# Internal_Breakout.net
KiCad netlist of a schematic drawn in EAGLE
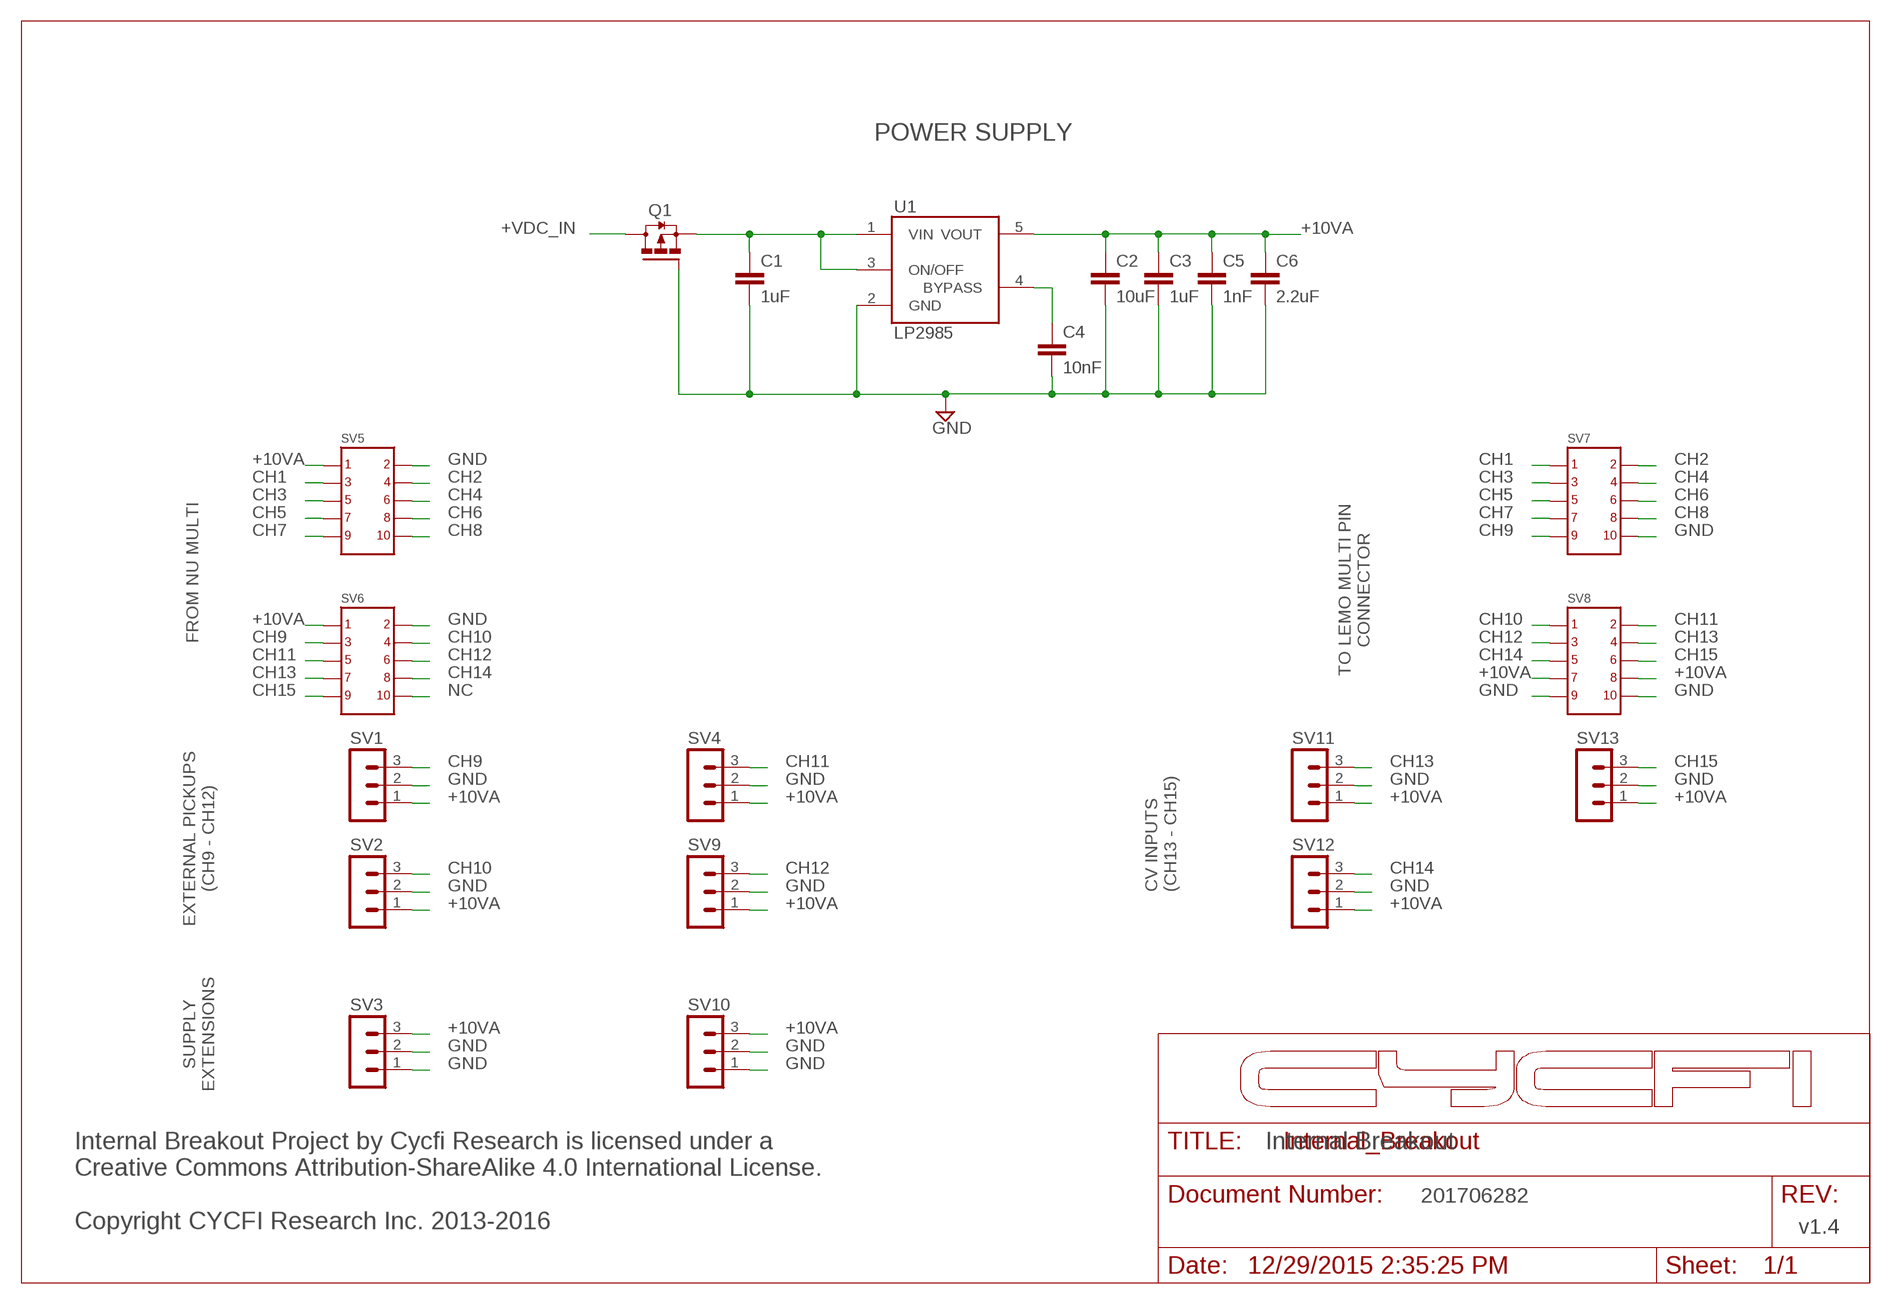
[diagram p0: schematic, sheet 1]

(export (version "E")
  (design (tool "Eeschema 10.0.6"))
  (components
    (comp (ref "C1")
      (value "1uF")
      (footprint "eagle-import:C0603")
      (libsource (lib "eagle-import") (part "C-EUC0603"))
    )
    (comp (ref "C2")
      (value "10uF")
      (footprint "eagle-import:C0603")
      (libsource (lib "eagle-import") (part "C-EUC0603"))
    )
    (comp (ref "C3")
      (value "1uF")
      (footprint "eagle-import:C0603")
      (libsource (lib "eagle-import") (part "C-EUC0603"))
    )
    (comp (ref "C4")
      (value "10nF")
      (footprint "eagle-import:C0402")
      (libsource (lib "eagle-import") (part "C-EUC0402"))
    )
    (comp (ref "C5")
      (value "1nF")
      (footprint "eagle-import:C0402")
      (libsource (lib "eagle-import") (part "C-EUC0402"))
    )
    (comp (ref "C6")
      (value "2.2uF")
      (footprint "eagle-import:C0603")
      (libsource (lib "eagle-import") (part "C-EUC0603"))
    )
    (comp (ref "Q1")
      (value "DMP3099L")
      (footprint "eagle-import:SUPER-SOT3")
      (libsource (lib "eagle-import") (part "FDN360P"))
    )
    (comp (ref "SV1")
      (value "MA03-1")
      (footprint "eagle-import:MA03-1")
      (libsource (lib "eagle-import") (part "MA03-1"))
    )
    (comp (ref "SV2")
      (value "MA03-1")
      (footprint "eagle-import:MA03-1")
      (libsource (lib "eagle-import") (part "MA03-1"))
    )
    (comp (ref "SV3")
      (value "MA03-1")
      (footprint "eagle-import:MA03-1")
      (libsource (lib "eagle-import") (part "MA03-1"))
    )
    (comp (ref "SV4")
      (value "MA03-1")
      (footprint "eagle-import:MA03-1")
      (libsource (lib "eagle-import") (part "MA03-1"))
    )
    (comp (ref "SV5")
      (value "2X5")
      (footprint "eagle-import:2X5")
      (libsource (lib "eagle-import") (part "2X5"))
    )
    (comp (ref "SV6")
      (value "2X5")
      (footprint "eagle-import:2X5")
      (libsource (lib "eagle-import") (part "2X5"))
    )
    (comp (ref "SV7")
      (value "2X5")
      (footprint "eagle-import:2X5")
      (libsource (lib "eagle-import") (part "2X5"))
    )
    (comp (ref "SV8")
      (value "2X5")
      (footprint "eagle-import:2X5")
      (libsource (lib "eagle-import") (part "2X5"))
    )
    (comp (ref "SV9")
      (value "MA03-1")
      (footprint "eagle-import:MA03-1")
      (libsource (lib "eagle-import") (part "MA03-1"))
    )
    (comp (ref "SV10")
      (value "MA03-1")
      (footprint "eagle-import:MA03-1")
      (libsource (lib "eagle-import") (part "MA03-1"))
    )
    (comp (ref "SV11")
      (value "MA03-1")
      (footprint "eagle-import:MA03-1")
      (libsource (lib "eagle-import") (part "MA03-1"))
    )
    (comp (ref "SV12")
      (value "MA03-1")
      (footprint "eagle-import:MA03-1")
      (libsource (lib "eagle-import") (part "MA03-1"))
    )
    (comp (ref "SV13")
      (value "MA03-1")
      (footprint "eagle-import:MA03-1")
      (libsource (lib "eagle-import") (part "MA03-1"))
    )
    (comp (ref "U1")
      (value "LP2985")
      (footprint "eagle-import:SOT25")
      (libsource (lib "eagle-import") (part "LP2985AIM5-3.3"))
    )
  )
  (nets
    (net (code "1") (name "/+VDC_IN") (class "Default")
      (node (ref "Q1") (pin "3") (pinfunction "D_3") (pintype "passive"))
      (node (ref "SV8") (pin "7") (pinfunction "7_7") (pintype "bidirectional"))
      (node (ref "SV8") (pin "8") (pinfunction "8_8") (pintype "bidirectional"))
    )
    (net (code "2") (name "/CH1") (class "Default")
      (node (ref "SV5") (pin "3") (pinfunction "3_3") (pintype "bidirectional"))
      (node (ref "SV7") (pin "1") (pinfunction "1_1") (pintype "bidirectional"))
    )
    (net (code "3") (name "/CH2") (class "Default")
      (node (ref "SV5") (pin "4") (pinfunction "4_4") (pintype "bidirectional"))
      (node (ref "SV7") (pin "2") (pinfunction "2_2") (pintype "bidirectional"))
    )
    (net (code "4") (name "/CH3") (class "Default")
      (node (ref "SV5") (pin "5") (pinfunction "5_5") (pintype "bidirectional"))
      (node (ref "SV7") (pin "3") (pinfunction "3_3") (pintype "bidirectional"))
    )
    (net (code "5") (name "/CH4") (class "Default")
      (node (ref "SV5") (pin "6") (pinfunction "6_6") (pintype "bidirectional"))
      (node (ref "SV7") (pin "4") (pinfunction "4_4") (pintype "bidirectional"))
    )
    (net (code "6") (name "/CH5") (class "Default")
      (node (ref "SV5") (pin "7") (pinfunction "7_7") (pintype "bidirectional"))
      (node (ref "SV7") (pin "5") (pinfunction "5_5") (pintype "bidirectional"))
    )
    (net (code "7") (name "/CH6") (class "Default")
      (node (ref "SV5") (pin "8") (pinfunction "8_8") (pintype "bidirectional"))
      (node (ref "SV7") (pin "6") (pinfunction "6_6") (pintype "bidirectional"))
    )
    (net (code "8") (name "/CH7") (class "Default")
      (node (ref "SV5") (pin "9") (pinfunction "9_9") (pintype "bidirectional"))
      (node (ref "SV7") (pin "7") (pinfunction "7_7") (pintype "bidirectional"))
    )
    (net (code "9") (name "/CH8") (class "Default")
      (node (ref "SV5") (pin "10") (pinfunction "10_10") (pintype "bidirectional"))
      (node (ref "SV7") (pin "8") (pinfunction "8_8") (pintype "bidirectional"))
    )
    (net (code "10") (name "/CH9") (class "Default")
      (node (ref "SV1") (pin "3") (pinfunction "3_3") (pintype "passive"))
      (node (ref "SV6") (pin "3") (pinfunction "3_3") (pintype "bidirectional"))
      (node (ref "SV7") (pin "9") (pinfunction "9_9") (pintype "bidirectional"))
    )
    (net (code "11") (name "/CH10") (class "Default")
      (node (ref "SV2") (pin "3") (pinfunction "3_3") (pintype "passive"))
      (node (ref "SV6") (pin "4") (pinfunction "4_4") (pintype "bidirectional"))
      (node (ref "SV8") (pin "1") (pinfunction "1_1") (pintype "bidirectional"))
    )
    (net (code "12") (name "/CH11") (class "Default")
      (node (ref "SV4") (pin "3") (pinfunction "3_3") (pintype "passive"))
      (node (ref "SV6") (pin "5") (pinfunction "5_5") (pintype "bidirectional"))
      (node (ref "SV8") (pin "2") (pinfunction "2_2") (pintype "bidirectional"))
    )
    (net (code "13") (name "/CH12") (class "Default")
      (node (ref "SV6") (pin "6") (pinfunction "6_6") (pintype "bidirectional"))
      (node (ref "SV8") (pin "3") (pinfunction "3_3") (pintype "bidirectional"))
      (node (ref "SV9") (pin "3") (pinfunction "3_3") (pintype "passive"))
    )
    (net (code "14") (name "/CH13") (class "Default")
      (node (ref "SV11") (pin "3") (pinfunction "3_3") (pintype "passive"))
      (node (ref "SV6") (pin "7") (pinfunction "7_7") (pintype "bidirectional"))
      (node (ref "SV8") (pin "4") (pinfunction "4_4") (pintype "bidirectional"))
    )
    (net (code "15") (name "/CH14") (class "Default")
      (node (ref "SV12") (pin "3") (pinfunction "3_3") (pintype "passive"))
      (node (ref "SV6") (pin "8") (pinfunction "8_8") (pintype "bidirectional"))
      (node (ref "SV8") (pin "5") (pinfunction "5_5") (pintype "bidirectional"))
    )
    (net (code "16") (name "/CH15") (class "Default")
      (node (ref "SV13") (pin "3") (pinfunction "3_3") (pintype "passive"))
      (node (ref "SV6") (pin "9") (pinfunction "9_9") (pintype "bidirectional"))
      (node (ref "SV8") (pin "6") (pinfunction "6_6") (pintype "bidirectional"))
    )
    (net (code "17") (name "/V+") (class "Default")
      (node (ref "C2") (pin "1") (pinfunction "1_1") (pintype "passive"))
      (node (ref "C3") (pin "1") (pinfunction "1_1") (pintype "passive"))
      (node (ref "C5") (pin "1") (pinfunction "1_1") (pintype "passive"))
      (node (ref "C6") (pin "1") (pinfunction "1_1") (pintype "passive"))
      (node (ref "SV1") (pin "1") (pinfunction "1_1") (pintype "passive"))
      (node (ref "SV10") (pin "3") (pinfunction "3_3") (pintype "passive"))
      (node (ref "SV11") (pin "1") (pinfunction "1_1") (pintype "passive"))
      (node (ref "SV12") (pin "1") (pinfunction "1_1") (pintype "passive"))
      (node (ref "SV13") (pin "1") (pinfunction "1_1") (pintype "passive"))
      (node (ref "SV2") (pin "1") (pinfunction "1_1") (pintype "passive"))
      (node (ref "SV3") (pin "3") (pinfunction "3_3") (pintype "passive"))
      (node (ref "SV4") (pin "1") (pinfunction "1_1") (pintype "passive"))
      (node (ref "SV5") (pin "1") (pinfunction "1_1") (pintype "bidirectional"))
      (node (ref "SV6") (pin "1") (pinfunction "1_1") (pintype "bidirectional"))
      (node (ref "SV9") (pin "1") (pinfunction "1_1") (pintype "passive"))
      (node (ref "U1") (pin "5") (pinfunction "VOUT_5") (pintype "power_in"))
    )
    (net (code "18") (name "GND") (class "Default")
      (node (ref "C1") (pin "2") (pinfunction "2_2") (pintype "passive"))
      (node (ref "C2") (pin "2") (pinfunction "2_2") (pintype "passive"))
      (node (ref "C3") (pin "2") (pinfunction "2_2") (pintype "passive"))
      (node (ref "C4") (pin "2") (pinfunction "2_2") (pintype "passive"))
      (node (ref "C5") (pin "2") (pinfunction "2_2") (pintype "passive"))
      (node (ref "C6") (pin "2") (pinfunction "2_2") (pintype "passive"))
      (node (ref "Q1") (pin "1") (pinfunction "G_1") (pintype "passive"))
      (node (ref "SV1") (pin "2") (pinfunction "2_2") (pintype "passive"))
      (node (ref "SV10") (pin "1") (pinfunction "1_1") (pintype "passive"))
      (node (ref "SV10") (pin "2") (pinfunction "2_2") (pintype "passive"))
      (node (ref "SV11") (pin "2") (pinfunction "2_2") (pintype "passive"))
      (node (ref "SV12") (pin "2") (pinfunction "2_2") (pintype "passive"))
      (node (ref "SV13") (pin "2") (pinfunction "2_2") (pintype "passive"))
      (node (ref "SV2") (pin "2") (pinfunction "2_2") (pintype "passive"))
      (node (ref "SV3") (pin "1") (pinfunction "1_1") (pintype "passive"))
      (node (ref "SV3") (pin "2") (pinfunction "2_2") (pintype "passive"))
      (node (ref "SV4") (pin "2") (pinfunction "2_2") (pintype "passive"))
      (node (ref "SV5") (pin "2") (pinfunction "2_2") (pintype "bidirectional"))
      (node (ref "SV6") (pin "2") (pinfunction "2_2") (pintype "bidirectional"))
      (node (ref "SV7") (pin "10") (pinfunction "10_10") (pintype "bidirectional"))
      (node (ref "SV8") (pin "10") (pinfunction "10_10") (pintype "bidirectional"))
      (node (ref "SV8") (pin "9") (pinfunction "9_9") (pintype "bidirectional"))
      (node (ref "SV9") (pin "2") (pinfunction "2_2") (pintype "passive"))
      (node (ref "U1") (pin "2") (pinfunction "GND_2") (pintype "power_in"))
    )
    (net (code "19") (name "Net-(Q1-S)") (class "Default")
      (node (ref "C1") (pin "1") (pinfunction "1_1") (pintype "passive"))
      (node (ref "Q1") (pin "2") (pinfunction "S_2") (pintype "passive"))
      (node (ref "U1") (pin "1") (pinfunction "VIN_1") (pintype "power_in"))
      (node (ref "U1") (pin "3") (pinfunction "ON/OFF_3") (pintype "input"))
    )
    (net (code "20") (name "Net-(U1-BYPASS)") (class "Default")
      (node (ref "C4") (pin "1") (pinfunction "1_1") (pintype "passive"))
      (node (ref "U1") (pin "4") (pinfunction "BYPASS_4") (pintype "power_in"))
    )
    (net (code "21") (name "unconnected-(SV6-Pad10)") (class "Default")
      (node (ref "SV6") (pin "10") (pinfunction "10_10") (pintype "bidirectional"))
    )
  )
)
